# back.net
KiCad netlist of a schematic drawn in EAGLE
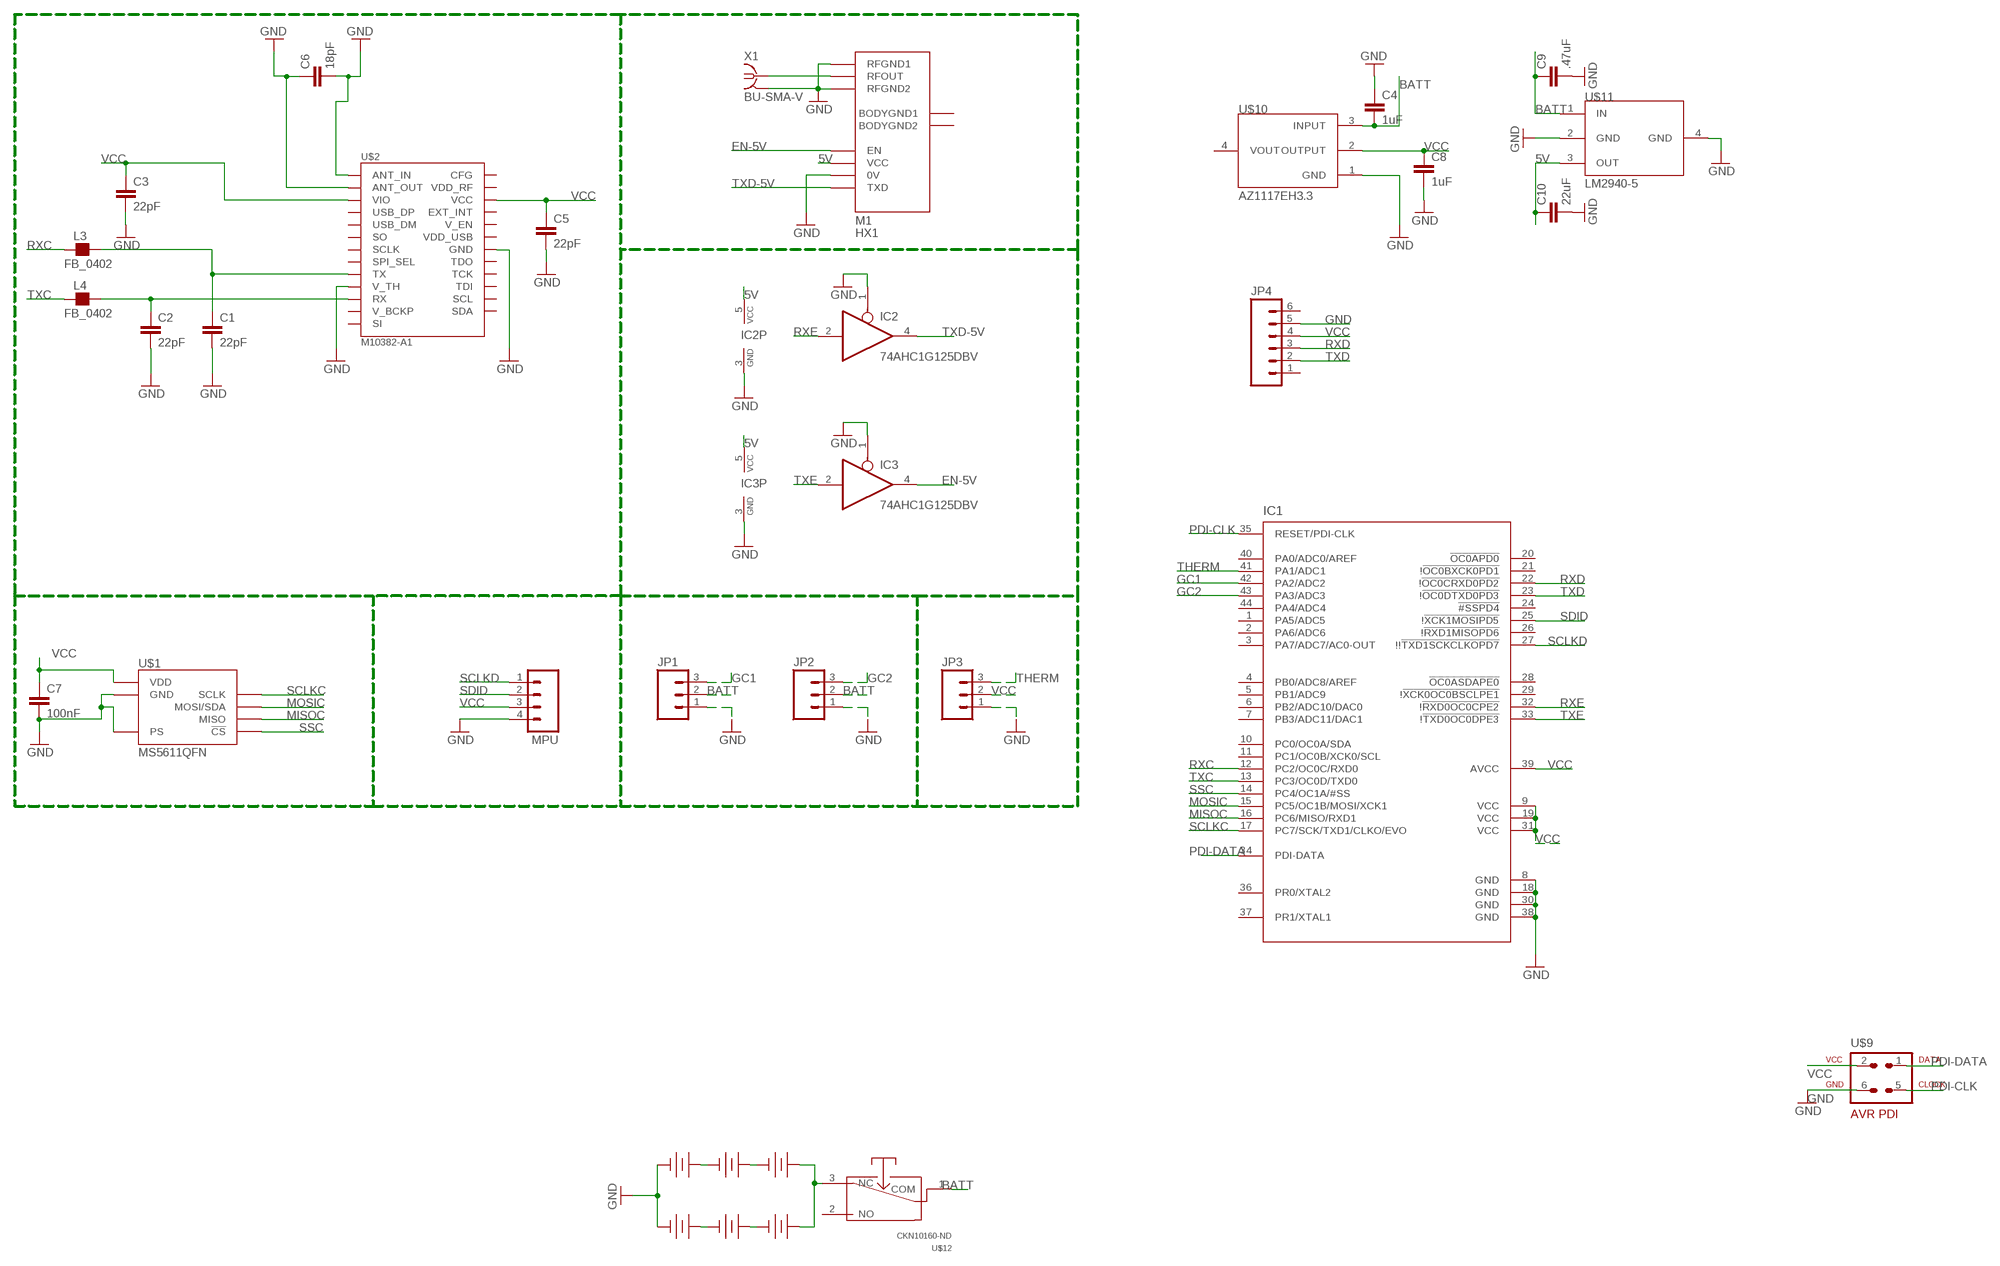
[diagram p0: schematic, sheet 1]

(export (version "E")
  (design (tool "Eeschema 10.0.6"))
  (components
    (comp (ref "C1")
      (value "22pF")
      (footprint "eagle-import:0805")
      (libsource (lib "eagle-import") (part "CAP0805"))
    )
    (comp (ref "C2")
      (value "22pF")
      (footprint "eagle-import:0805")
      (libsource (lib "eagle-import") (part "CAP0805"))
    )
    (comp (ref "C3")
      (value "22pF")
      (footprint "eagle-import:0805")
      (libsource (lib "eagle-import") (part "CAP0805"))
    )
    (comp (ref "C4")
      (value "1uF")
      (footprint "eagle-import:0603-CAP")
      (libsource (lib "eagle-import") (part "CAP0603-CAP"))
    )
    (comp (ref "C5")
      (value "22pF")
      (footprint "eagle-import:0805")
      (libsource (lib "eagle-import") (part "CAP0805"))
    )
    (comp (ref "C6")
      (value "18pF")
      (footprint "eagle-import:0805")
      (libsource (lib "eagle-import") (part "CAP0805"))
    )
    (comp (ref "C7")
      (value "100nF")
      (footprint "eagle-import:0805")
      (libsource (lib "eagle-import") (part "CAP0805"))
    )
    (comp (ref "C8")
      (value "1uF")
      (footprint "eagle-import:0603-CAP")
      (libsource (lib "eagle-import") (part "CAP0603-CAP"))
    )
    (comp (ref "C9")
      (value ".47uF")
      (footprint "eagle-import:0603-CAP")
      (libsource (lib "eagle-import") (part "CAP0603-CAP"))
    )
    (comp (ref "C10")
      (value "22uF")
      (footprint "eagle-import:0603-CAP")
      (libsource (lib "eagle-import") (part "CAP0603-CAP"))
    )
    (comp (ref "IC1")
      (value "AT-XMEGA-XXA4-AU")
      (footprint "eagle-import:QFP80P1200X1200X120-44N")
      (libsource (lib "eagle-import") (part "AT-XMEGA-XXA4-AU"))
    )
    (comp (ref "IC2")
      (value "74AHC1G125DBV")
      (footprint "eagle-import:SOT23-5")
      (libsource (lib "eagle-import") (part "741G125DBVAHC"))
    )
    (comp (ref "IC3")
      (value "74AHC1G125DBV")
      (footprint "eagle-import:SOT23-5")
      (libsource (lib "eagle-import") (part "741G125DBVAHC"))
    )
    (comp (ref "JP1")
      (value "M03JST-PTH")
      (footprint "eagle-import:JST-3-PTH")
      (libsource (lib "eagle-import") (part "M03JST-PTH"))
    )
    (comp (ref "JP2")
      (value "M03JST-PTH")
      (footprint "eagle-import:JST-3-PTH")
      (libsource (lib "eagle-import") (part "M03JST-PTH"))
    )
    (comp (ref "JP3")
      (value "M03JST-PTH")
      (footprint "eagle-import:JST-3-PTH")
      (libsource (lib "eagle-import") (part "M03JST-PTH"))
    )
    (comp (ref "JP4")
      (value "M06POLAR")
      (footprint "eagle-import:MOLEX-1X6")
      (libsource (lib "eagle-import") (part "M06POLAR"))
    )
    (comp (ref "L3")
      (value "FB_0402")
      (footprint "eagle-import:L0402")
      (libsource (lib "eagle-import") (part "FB_0402"))
    )
    (comp (ref "L4")
      (value "FB_0402")
      (footprint "eagle-import:L0402")
      (libsource (lib "eagle-import") (part "FB_0402"))
    )
    (comp (ref "M1")
      (value "HX1")
      (footprint "eagle-import:HX1")
      (libsource (lib "eagle-import") (part "HX1"))
    )
    (comp (ref "MPU")
      (value "M04")
      (footprint "eagle-import:04P")
      (libsource (lib "eagle-import") (part "M04"))
    )
    (comp (ref "U$1")
      (value "MS5611QFN")
      (footprint "eagle-import:MS5611-01BA01")
      (libsource (lib "eagle-import") (part "MS5611QFN"))
    )
    (comp (ref "U$2")
      (value "M10382-A1")
      (footprint "eagle-import:M10382-A1")
      (libsource (lib "eagle-import") (part "M10382-A1"))
    )
    (comp (ref "U$3")
      (value "123_BATTERY_HOLDERCR-123-A")
      (footprint "eagle-import:CR-123-A_HOLDER")
      (libsource (lib "eagle-import") (part "123_BATTERY_HOLDERCR-123-A"))
    )
    (comp (ref "U$4")
      (value "123_BATTERY_HOLDERCR-123-A")
      (footprint "eagle-import:CR-123-A_HOLDER")
      (libsource (lib "eagle-import") (part "123_BATTERY_HOLDERCR-123-A"))
    )
    (comp (ref "U$5")
      (value "123_BATTERY_HOLDERCR-123-A")
      (footprint "eagle-import:CR-123-A_HOLDER")
      (libsource (lib "eagle-import") (part "123_BATTERY_HOLDERCR-123-A"))
    )
    (comp (ref "U$6")
      (value "123_BATTERY_HOLDERCR-123-A")
      (footprint "eagle-import:CR-123-A_HOLDER")
      (libsource (lib "eagle-import") (part "123_BATTERY_HOLDERCR-123-A"))
    )
    (comp (ref "U$7")
      (value "123_BATTERY_HOLDERCR-123-A")
      (footprint "eagle-import:CR-123-A_HOLDER")
      (libsource (lib "eagle-import") (part "123_BATTERY_HOLDERCR-123-A"))
    )
    (comp (ref "U$8")
      (value "123_BATTERY_HOLDERCR-123-A")
      (footprint "eagle-import:CR-123-A_HOLDER")
      (libsource (lib "eagle-import") (part "123_BATTERY_HOLDERCR-123-A"))
    )
    (comp (ref "U$9")
      (value "AVR-PDIVERT")
      (footprint "eagle-import:AVR-ISP-6")
      (libsource (lib "eagle-import") (part "AVR-PDIVERT"))
    )
    (comp (ref "U$10")
      (value "AZ1117EH3.3")
      (footprint "eagle-import:SOT-223")
      (libsource (lib "eagle-import") (part "AZ1117EH3.3"))
    )
    (comp (ref "U$11")
      (value "LM2940-5")
      (footprint "eagle-import:SOT-223")
      (libsource (lib "eagle-import") (part "LM2940-5"))
    )
    (comp (ref "U$12")
      (value "CKN10160-ND")
      (footprint "eagle-import:ZMCHFL3R")
      (libsource (lib "eagle-import") (part "CKN10160-ND"))
    )
    (comp (ref "X1")
      (value "BU-SMA-V")
      (footprint "eagle-import:BU-SMA-V")
      (libsource (lib "eagle-import") (part "BU-SMA-V"))
    )
  )
  (nets
    (net (code "1") (name "/5V") (class "Default")
      (node (ref "C10") (pin "1") (pinfunction "1_1") (pintype "passive"))
      (node (ref "IC2") (pin "5") (pinfunction "VCC_5") (pintype "power_in"))
      (node (ref "IC3") (pin "5") (pinfunction "VCC_5") (pintype "power_in"))
      (node (ref "M1") (pin "VCC") (pinfunction "VCC_VCC") (pintype "bidirectional"))
      (node (ref "U$11") (pin "3") (pinfunction "OUT_3") (pintype "bidirectional"))
    )
    (net (code "2") (name "/BATT") (class "Default")
      (node (ref "C4") (pin "2") (pinfunction "2_2") (pintype "passive"))
      (node (ref "C9") (pin "1") (pinfunction "1_1") (pintype "passive"))
      (node (ref "JP1") (pin "2") (pinfunction "2_2") (pintype "passive"))
      (node (ref "JP2") (pin "2") (pinfunction "2_2") (pintype "passive"))
      (node (ref "U$10") (pin "3") (pinfunction "INPUT_3") (pintype "bidirectional"))
      (node (ref "U$11") (pin "1") (pinfunction "IN_1") (pintype "bidirectional"))
      (node (ref "U$12") (pin "1") (pinfunction "COM_1") (pintype "bidirectional"))
    )
    (net (code "3") (name "/EN-5V") (class "Default")
      (node (ref "IC3") (pin "4") (pinfunction "O_4") (pintype "tri_state"))
      (node (ref "M1") (pin "EN") (pinfunction "EN_EN") (pintype "bidirectional"))
    )
    (net (code "4") (name "/GC1") (class "Default")
      (node (ref "IC1") (pin "42") (pinfunction "PA2/ADC2_42") (pintype "bidirectional"))
      (node (ref "JP1") (pin "3") (pinfunction "3_3") (pintype "passive"))
    )
    (net (code "5") (name "/GC2") (class "Default")
      (node (ref "IC1") (pin "43") (pinfunction "PA3/ADC3_43") (pintype "bidirectional"))
      (node (ref "JP2") (pin "3") (pinfunction "3_3") (pintype "passive"))
    )
    (net (code "6") (name "/MISOC") (class "Default")
      (node (ref "IC1") (pin "16") (pinfunction "PC6/MISO/RXD1_16") (pintype "bidirectional"))
      (node (ref "U$1") (pin "6") (pinfunction "MISO_6") (pintype "bidirectional"))
    )
    (net (code "7") (name "/MOSIC") (class "Default")
      (node (ref "IC1") (pin "15") (pinfunction "PC5/OC1B/MOSI/XCK1_15") (pintype "bidirectional"))
      (node (ref "U$1") (pin "7") (pinfunction "MOSI/SDA_7") (pintype "bidirectional"))
    )
    (net (code "8") (name "/PDI-CLK") (class "Default")
      (node (ref "IC1") (pin "35") (pinfunction "RESET/PDI-CLK_35") (pintype "input"))
      (node (ref "U$9") (pin "5") (pinfunction "5_5") (pintype "passive"))
    )
    (net (code "9") (name "/PDI-DATA") (class "Default")
      (node (ref "IC1") (pin "34") (pinfunction "PDI-DATA_34") (pintype "bidirectional"))
      (node (ref "U$9") (pin "1") (pinfunction "1_1") (pintype "passive"))
    )
    (net (code "10") (name "/RXC") (class "Default")
      (node (ref "IC1") (pin "12") (pinfunction "PC2/OC0C/RXD0_12") (pintype "bidirectional"))
      (node (ref "L3") (pin "1") (pinfunction "1_1") (pintype "passive"))
    )
    (net (code "11") (name "/RXD") (class "Default")
      (node (ref "IC1") (pin "22") (pinfunction "~OC0CRXD0PD2_22") (pintype "bidirectional"))
      (node (ref "JP4") (pin "3") (pinfunction "3_3") (pintype "passive"))
    )
    (net (code "12") (name "/RXE") (class "Default")
      (node (ref "IC1") (pin "32") (pinfunction "~RXD0OC0CPE2_32") (pintype "bidirectional"))
      (node (ref "IC2") (pin "2") (pinfunction "I_2") (pintype "input"))
    )
    (net (code "13") (name "/SCLKC") (class "Default")
      (node (ref "IC1") (pin "17") (pinfunction "PC7/SCK/TXD1/CLKO/EVO_17") (pintype "bidirectional"))
      (node (ref "U$1") (pin "8") (pinfunction "SCLK_8") (pintype "bidirectional"))
    )
    (net (code "14") (name "/SCLKD") (class "Default")
      (node (ref "IC1") (pin "27") (pinfunction "~~{TXD1SCKCLKOPD7}_27") (pintype "bidirectional"))
      (node (ref "MPU") (pin "1") (pinfunction "1_1") (pintype "passive"))
    )
    (net (code "15") (name "/SDID") (class "Default")
      (node (ref "IC1") (pin "25") (pinfunction "~XCK1MOSIPD5_25") (pintype "bidirectional"))
      (node (ref "MPU") (pin "2") (pinfunction "2_2") (pintype "passive"))
    )
    (net (code "16") (name "/SSC") (class "Default")
      (node (ref "IC1") (pin "14") (pinfunction "PC4/OC1A/#SS_14") (pintype "bidirectional"))
      (node (ref "U$1") (pin "4") (pinfunction "~{CS}_4") (pintype "bidirectional"))
      (node (ref "U$1") (pin "5") (pinfunction "~{CS}_5") (pintype "bidirectional"))
    )
    (net (code "17") (name "/THERM") (class "Default")
      (node (ref "IC1") (pin "41") (pinfunction "PA1/ADC1_41") (pintype "bidirectional"))
      (node (ref "JP3") (pin "3") (pinfunction "3_3") (pintype "passive"))
    )
    (net (code "18") (name "/TXC") (class "Default")
      (node (ref "IC1") (pin "13") (pinfunction "PC3/OC0D/TXD0_13") (pintype "bidirectional"))
      (node (ref "L4") (pin "1") (pinfunction "1_1") (pintype "passive"))
    )
    (net (code "19") (name "/TXD") (class "Default")
      (node (ref "IC1") (pin "23") (pinfunction "~OC0DTXD0PD3_23") (pintype "bidirectional"))
      (node (ref "JP4") (pin "2") (pinfunction "2_2") (pintype "passive"))
    )
    (net (code "20") (name "/TXD-5V") (class "Default")
      (node (ref "IC2") (pin "4") (pinfunction "O_4") (pintype "tri_state"))
      (node (ref "M1") (pin "TXD") (pinfunction "TXD_TXD") (pintype "bidirectional"))
    )
    (net (code "21") (name "/TXE") (class "Default")
      (node (ref "IC1") (pin "33") (pinfunction "~TXD0OC0DPE3_33") (pintype "bidirectional"))
      (node (ref "IC3") (pin "2") (pinfunction "I_2") (pintype "input"))
    )
    (net (code "22") (name "/VCC") (class "Default")
      (node (ref "C3") (pin "1") (pinfunction "1_1") (pintype "passive"))
      (node (ref "C5") (pin "1") (pinfunction "1_1") (pintype "passive"))
      (node (ref "C7") (pin "1") (pinfunction "1_1") (pintype "passive"))
      (node (ref "C8") (pin "1") (pinfunction "1_1") (pintype "passive"))
      (node (ref "IC1") (pin "19") (pinfunction "VCC_19") (pintype "power_in"))
      (node (ref "IC1") (pin "31") (pinfunction "VCC_31") (pintype "power_in"))
      (node (ref "IC1") (pin "39") (pinfunction "AVCC_39") (pintype "power_in"))
      (node (ref "IC1") (pin "9") (pinfunction "VCC_9") (pintype "power_in"))
      (node (ref "JP3") (pin "2") (pinfunction "2_2") (pintype "passive"))
      (node (ref "JP4") (pin "4") (pinfunction "4_4") (pintype "passive"))
      (node (ref "MPU") (pin "3") (pinfunction "3_3") (pintype "passive"))
      (node (ref "U$1") (pin "1") (pinfunction "VDD_1") (pintype "bidirectional"))
      (node (ref "U$10") (pin "2") (pinfunction "OUTPUT_2") (pintype "bidirectional"))
      (node (ref "U$2") (pin "27") (pinfunction "VCC_27") (pintype "bidirectional"))
      (node (ref "U$2") (pin "5") (pinfunction "VIO_5") (pintype "bidirectional"))
      (node (ref "U$9") (pin "2") (pinfunction "2_2") (pintype "passive"))
    )
    (net (code "23") (name "GND") (class "Default")
      (node (ref "C1") (pin "2") (pinfunction "2_2") (pintype "passive"))
      (node (ref "C10") (pin "2") (pinfunction "2_2") (pintype "passive"))
      (node (ref "C2") (pin "2") (pinfunction "2_2") (pintype "passive"))
      (node (ref "C3") (pin "2") (pinfunction "2_2") (pintype "passive"))
      (node (ref "C4") (pin "1") (pinfunction "1_1") (pintype "passive"))
      (node (ref "C5") (pin "2") (pinfunction "2_2") (pintype "passive"))
      (node (ref "C6") (pin "1") (pinfunction "1_1") (pintype "passive"))
      (node (ref "C6") (pin "2") (pinfunction "2_2") (pintype "passive"))
      (node (ref "C7") (pin "2") (pinfunction "2_2") (pintype "passive"))
      (node (ref "C8") (pin "2") (pinfunction "2_2") (pintype "passive"))
      (node (ref "C9") (pin "2") (pinfunction "2_2") (pintype "passive"))
      (node (ref "IC1") (pin "18") (pinfunction "GND_18") (pintype "power_in"))
      (node (ref "IC1") (pin "30") (pinfunction "GND_30") (pintype "power_in"))
      (node (ref "IC1") (pin "38") (pinfunction "GND_38") (pintype "power_in"))
      (node (ref "IC1") (pin "8") (pinfunction "GND_8") (pintype "power_in"))
      (node (ref "IC2") (pin "1") (pinfunction "OE_1") (pintype "input"))
      (node (ref "IC2") (pin "3") (pinfunction "GND_3") (pintype "power_in"))
      (node (ref "IC3") (pin "1") (pinfunction "OE_1") (pintype "input"))
      (node (ref "IC3") (pin "3") (pinfunction "GND_3") (pintype "power_in"))
      (node (ref "JP1") (pin "1") (pinfunction "1_1") (pintype "passive"))
      (node (ref "JP2") (pin "1") (pinfunction "1_1") (pintype "passive"))
      (node (ref "JP3") (pin "1") (pinfunction "1_1") (pintype "passive"))
      (node (ref "JP4") (pin "5") (pinfunction "5_5") (pintype "passive"))
      (node (ref "M1") (pin "0V") (pinfunction "0V_0V") (pintype "bidirectional"))
      (node (ref "M1") (pin "RFGND1") (pinfunction "RFGND1_RFGND1") (pintype "bidirectional"))
      (node (ref "M1") (pin "RFGND2") (pinfunction "RFGND2_RFGND2") (pintype "bidirectional"))
      (node (ref "MPU") (pin "4") (pinfunction "4_4") (pintype "passive"))
      (node (ref "U$1") (pin "2") (pinfunction "PS_2") (pintype "bidirectional"))
      (node (ref "U$1") (pin "3") (pinfunction "GND_3") (pintype "bidirectional"))
      (node (ref "U$10") (pin "1") (pinfunction "GND_1") (pintype "bidirectional"))
      (node (ref "U$11") (pin "2") (pinfunction "GND_2") (pintype "bidirectional"))
      (node (ref "U$11") (pin "4") (pinfunction "GND_4") (pintype "bidirectional"))
      (node (ref "U$2") (pin "1") (pinfunction "ANT_IN_1") (pintype "bidirectional"))
      (node (ref "U$2") (pin "12") (pinfunction "V_TH_12") (pintype "bidirectional"))
      (node (ref "U$2") (pin "14") (pinfunction "GND_14") (pintype "bidirectional"))
      (node (ref "U$2") (pin "17") (pinfunction "GND_17") (pintype "bidirectional"))
      (node (ref "U$2") (pin "2") (pinfunction "GND_2") (pintype "bidirectional"))
      (node (ref "U$2") (pin "21") (pinfunction "GND_21") (pintype "bidirectional"))
      (node (ref "U$2") (pin "24") (pinfunction "GND_24") (pintype "bidirectional"))
      (node (ref "U$2") (pin "26") (pinfunction "GND_26") (pintype "bidirectional"))
      (node (ref "U$2") (pin "28") (pinfunction "GND_28") (pintype "bidirectional"))
      (node (ref "U$2") (pin "3") (pinfunction "ANT_OUT_3") (pintype "bidirectional"))
      (node (ref "U$2") (pin "33") (pinfunction "GND_33") (pintype "bidirectional"))
      (node (ref "U$2") (pin "34") (pinfunction "GND_34") (pintype "bidirectional"))
      (node (ref "U$2") (pin "35") (pinfunction "GND_35") (pintype "bidirectional"))
      (node (ref "U$2") (pin "36") (pinfunction "GND_36") (pintype "bidirectional"))
      (node (ref "U$2") (pin "4") (pinfunction "GND_4") (pintype "bidirectional"))
      (node (ref "U$3") (pin "-") (pinfunction "-_-") (pintype "bidirectional"))
      (node (ref "U$6") (pin "-") (pinfunction "-_-") (pintype "bidirectional"))
      (node (ref "U$9") (pin "6") (pinfunction "6_6") (pintype "passive"))
      (node (ref "X1") (pin "2") (pinfunction "GND_2") (pintype "power_in"))
    )
    (net (code "24") (name "Net-(M1-PadRFOUT)") (class "Default")
      (node (ref "M1") (pin "RFOUT") (pinfunction "RFOUT_RFOUT") (pintype "bidirectional"))
      (node (ref "X1") (pin "1") (pinfunction "1_1") (pintype "passive"))
    )
    (net (code "25") (name "Net-(U$2-RX)") (class "Default")
      (node (ref "C2") (pin "1") (pinfunction "1_1") (pintype "passive"))
      (node (ref "L4") (pin "2") (pinfunction "2_2") (pintype "passive"))
      (node (ref "U$2") (pin "13") (pinfunction "RX_13") (pintype "bidirectional"))
    )
    (net (code "26") (name "Net-(U$2-TX)") (class "Default")
      (node (ref "C1") (pin "1") (pinfunction "1_1") (pintype "passive"))
      (node (ref "L3") (pin "2") (pinfunction "2_2") (pintype "passive"))
      (node (ref "U$2") (pin "11") (pinfunction "TX_11") (pintype "bidirectional"))
    )
    (net (code "27") (name "Net-(U$3-Pad+)") (class "Default")
      (node (ref "U$3") (pin "+") (pinfunction "+_+") (pintype "bidirectional"))
      (node (ref "U$4") (pin "-") (pinfunction "-_-") (pintype "bidirectional"))
    )
    (net (code "28") (name "Net-(U$4-Pad+)") (class "Default")
      (node (ref "U$4") (pin "+") (pinfunction "+_+") (pintype "bidirectional"))
      (node (ref "U$5") (pin "-") (pinfunction "-_-") (pintype "bidirectional"))
    )
    (net (code "29") (name "Net-(U$6-Pad+)") (class "Default")
      (node (ref "U$6") (pin "+") (pinfunction "+_+") (pintype "bidirectional"))
      (node (ref "U$7") (pin "-") (pinfunction "-_-") (pintype "bidirectional"))
    )
    (net (code "30") (name "Net-(U$7-Pad+)") (class "Default")
      (node (ref "U$7") (pin "+") (pinfunction "+_+") (pintype "bidirectional"))
      (node (ref "U$8") (pin "-") (pinfunction "-_-") (pintype "bidirectional"))
    )
    (net (code "31") (name "Net-(U$12-NC)") (class "Default")
      (node (ref "U$12") (pin "3") (pinfunction "NC_3") (pintype "bidirectional"))
      (node (ref "U$5") (pin "+") (pinfunction "+_+") (pintype "bidirectional"))
      (node (ref "U$8") (pin "+") (pinfunction "+_+") (pintype "bidirectional"))
    )
    (net (code "32") (name "unconnected-(IC1-PA0{slash}ADC0{slash}AREF-Pad40)") (class "Default")
      (node (ref "IC1") (pin "40") (pinfunction "PA0/ADC0/AREF_40") (pintype "bidirectional"))
    )
    (net (code "33") (name "unconnected-(IC1-PA4{slash}ADC4-Pad44)") (class "Default")
      (node (ref "IC1") (pin "44") (pinfunction "PA4/ADC4_44") (pintype "bidirectional"))
    )
    (net (code "34") (name "unconnected-(IC1-PA5{slash}ADC5-Pad1)") (class "Default")
      (node (ref "IC1") (pin "1") (pinfunction "PA5/ADC5_1") (pintype "bidirectional"))
    )
    (net (code "35") (name "unconnected-(IC1-PA6{slash}ADC6-Pad2)") (class "Default")
      (node (ref "IC1") (pin "2") (pinfunction "PA6/ADC6_2") (pintype "bidirectional"))
    )
    (net (code "36") (name "unconnected-(IC1-PA7{slash}ADC7{slash}AC0-OUT-Pad3)") (class "Default")
      (node (ref "IC1") (pin "3") (pinfunction "PA7/ADC7/AC0-OUT_3") (pintype "bidirectional"))
    )
    (net (code "37") (name "unconnected-(IC1-PB0{slash}ADC8{slash}AREF-Pad4)") (class "Default")
      (node (ref "IC1") (pin "4") (pinfunction "PB0/ADC8/AREF_4") (pintype "bidirectional"))
    )
    (net (code "38") (name "unconnected-(IC1-PB1{slash}ADC9-Pad5)") (class "Default")
      (node (ref "IC1") (pin "5") (pinfunction "PB1/ADC9_5") (pintype "bidirectional"))
    )
    (net (code "39") (name "unconnected-(IC1-PB2{slash}ADC10{slash}DAC0-Pad6)") (class "Default")
      (node (ref "IC1") (pin "6") (pinfunction "PB2/ADC10/DAC0_6") (pintype "bidirectional"))
    )
    (net (code "40") (name "unconnected-(IC1-PB3{slash}ADC11{slash}DAC1-Pad7)") (class "Default")
      (node (ref "IC1") (pin "7") (pinfunction "PB3/ADC11/DAC1_7") (pintype "bidirectional"))
    )
    (net (code "41") (name "unconnected-(IC1-PC0{slash}OC0A{slash}SDA-Pad10)") (class "Default")
      (node (ref "IC1") (pin "10") (pinfunction "PC0/OC0A/SDA_10") (pintype "bidirectional"))
    )
    (net (code "42") (name "unconnected-(IC1-PC1{slash}OC0B{slash}XCK0{slash}SCL-Pad11)") (class "Default")
      (node (ref "IC1") (pin "11") (pinfunction "PC1/OC0B/XCK0/SCL_11") (pintype "bidirectional"))
    )
    (net (code "43") (name "unconnected-(IC1-PR0{slash}XTAL2-Pad36)") (class "Default")
      (node (ref "IC1") (pin "36") (pinfunction "PR0/XTAL2_36") (pintype "bidirectional"))
    )
    (net (code "44") (name "unconnected-(IC1-PR1{slash}XTAL1-Pad37)") (class "Default")
      (node (ref "IC1") (pin "37") (pinfunction "PR1/XTAL1_37") (pintype "bidirectional"))
    )
    (net (code "45") (name "unconnected-(IC1-~OC0BXCK0PD1-Pad21)") (class "Default")
      (node (ref "IC1") (pin "21") (pinfunction "~OC0BXCK0PD1_21") (pintype "bidirectional"))
    )
    (net (code "46") (name "unconnected-(IC1-~RXD1MISOPD6-Pad26)") (class "Default")
      (node (ref "IC1") (pin "26") (pinfunction "~RXD1MISOPD6_26") (pintype "bidirectional"))
    )
    (net (code "47") (name "unconnected-(IC1-~XCK0OC0BSCLPE1-Pad29)") (class "Default")
      (node (ref "IC1") (pin "29") (pinfunction "~XCK0OC0BSCLPE1_29") (pintype "bidirectional"))
    )
    (net (code "48") (name "unconnected-(IC1-~{#SSPD4}-Pad24)") (class "Default")
      (node (ref "IC1") (pin "24") (pinfunction "~{#SSPD4}_24") (pintype "bidirectional"))
    )
    (net (code "49") (name "unconnected-(IC1-~{OC0APD0}-Pad20)") (class "Default")
      (node (ref "IC1") (pin "20") (pinfunction "~{OC0APD0}_20") (pintype "bidirectional"))
    )
    (net (code "50") (name "unconnected-(IC1-~{OC0ASDAPE0}-Pad28)") (class "Default")
      (node (ref "IC1") (pin "28") (pinfunction "~{OC0ASDAPE0}_28") (pintype "bidirectional"))
    )
    (net (code "51") (name "unconnected-(JP4-Pad1)") (class "Default")
      (node (ref "JP4") (pin "1") (pinfunction "1_1") (pintype "passive"))
    )
    (net (code "52") (name "unconnected-(JP4-Pad6)") (class "Default")
      (node (ref "JP4") (pin "6") (pinfunction "6_6") (pintype "passive"))
    )
    (net (code "53") (name "unconnected-(M1-PadBODYGND1)") (class "Default")
      (node (ref "M1") (pin "BODYGND1") (pinfunction "BODYGND1_BODYGND1") (pintype "bidirectional"))
    )
    (net (code "54") (name "unconnected-(M1-PadBODYGND2)") (class "Default")
      (node (ref "M1") (pin "BODYGND2") (pinfunction "BODYGND2_BODYGND2") (pintype "bidirectional"))
    )
    (net (code "55") (name "unconnected-(U$2-CFG-Pad31)") (class "Default")
      (node (ref "U$2") (pin "31") (pinfunction "CFG_31") (pintype "bidirectional"))
    )
    (net (code "56") (name "unconnected-(U$2-EXT_INT-Pad29)") (class "Default")
      (node (ref "U$2") (pin "29") (pinfunction "EXT_INT_29") (pintype "bidirectional"))
    )
    (net (code "57") (name "unconnected-(U$2-SCL-Pad19)") (class "Default")
      (node (ref "U$2") (pin "19") (pinfunction "SCL_19") (pintype "bidirectional"))
    )
    (net (code "58") (name "unconnected-(U$2-SCLK-Pad9)") (class "Default")
      (node (ref "U$2") (pin "9") (pinfunction "SCLK_9") (pintype "bidirectional"))
    )
    (net (code "59") (name "unconnected-(U$2-SDA-Pad18)") (class "Default")
      (node (ref "U$2") (pin "18") (pinfunction "SDA_18") (pintype "bidirectional"))
    )
    (net (code "60") (name "unconnected-(U$2-SI-Pad16)") (class "Default")
      (node (ref "U$2") (pin "16") (pinfunction "SI_16") (pintype "bidirectional"))
    )
    (net (code "61") (name "unconnected-(U$2-SO-Pad8)") (class "Default")
      (node (ref "U$2") (pin "8") (pinfunction "SO_8") (pintype "bidirectional"))
    )
    (net (code "62") (name "unconnected-(U$2-SPI_SEL-Pad10)") (class "Default")
      (node (ref "U$2") (pin "10") (pinfunction "SPI_SEL_10") (pintype "bidirectional"))
    )
    (net (code "63") (name "unconnected-(U$2-TCK-Pad22)") (class "Default")
      (node (ref "U$2") (pin "22") (pinfunction "TCK_22") (pintype "bidirectional"))
    )
    (net (code "64") (name "unconnected-(U$2-TDI-Pad20)") (class "Default")
      (node (ref "U$2") (pin "20") (pinfunction "TDI_20") (pintype "bidirectional"))
    )
    (net (code "65") (name "unconnected-(U$2-TDO-Pad23)") (class "Default")
      (node (ref "U$2") (pin "23") (pinfunction "TDO_23") (pintype "bidirectional"))
    )
    (net (code "66") (name "unconnected-(U$2-USB_DM-Pad7)") (class "Default")
      (node (ref "U$2") (pin "7") (pinfunction "USB_DM_7") (pintype "bidirectional"))
    )
    (net (code "67") (name "unconnected-(U$2-USB_DP-Pad6)") (class "Default")
      (node (ref "U$2") (pin "6") (pinfunction "USB_DP_6") (pintype "bidirectional"))
    )
    (net (code "68") (name "unconnected-(U$2-VDD_RF-Pad25)") (class "Default")
      (node (ref "U$2") (pin "25") (pinfunction "VDD_RF_25") (pintype "bidirectional"))
    )
    (net (code "69") (name "unconnected-(U$2-VDD_USB-Pad32)") (class "Default")
      (node (ref "U$2") (pin "32") (pinfunction "VDD_USB_32") (pintype "bidirectional"))
    )
    (net (code "70") (name "unconnected-(U$2-V_BCKP-Pad15)") (class "Default")
      (node (ref "U$2") (pin "15") (pinfunction "V_BCKP_15") (pintype "bidirectional"))
    )
    (net (code "71") (name "unconnected-(U$2-V_EN-Pad30)") (class "Default")
      (node (ref "U$2") (pin "30") (pinfunction "V_EN_30") (pintype "bidirectional"))
    )
    (net (code "72") (name "unconnected-(U$10-VOUT-Pad4)") (class "Default")
      (node (ref "U$10") (pin "4") (pinfunction "VOUT_4") (pintype "bidirectional"))
    )
    (net (code "73") (name "unconnected-(U$12-NO-Pad2)") (class "Default")
      (node (ref "U$12") (pin "2") (pinfunction "NO_2") (pintype "bidirectional"))
    )
  )
)
